# eeZeePower.net
KiCad netlist of a schematic drawn in EAGLE
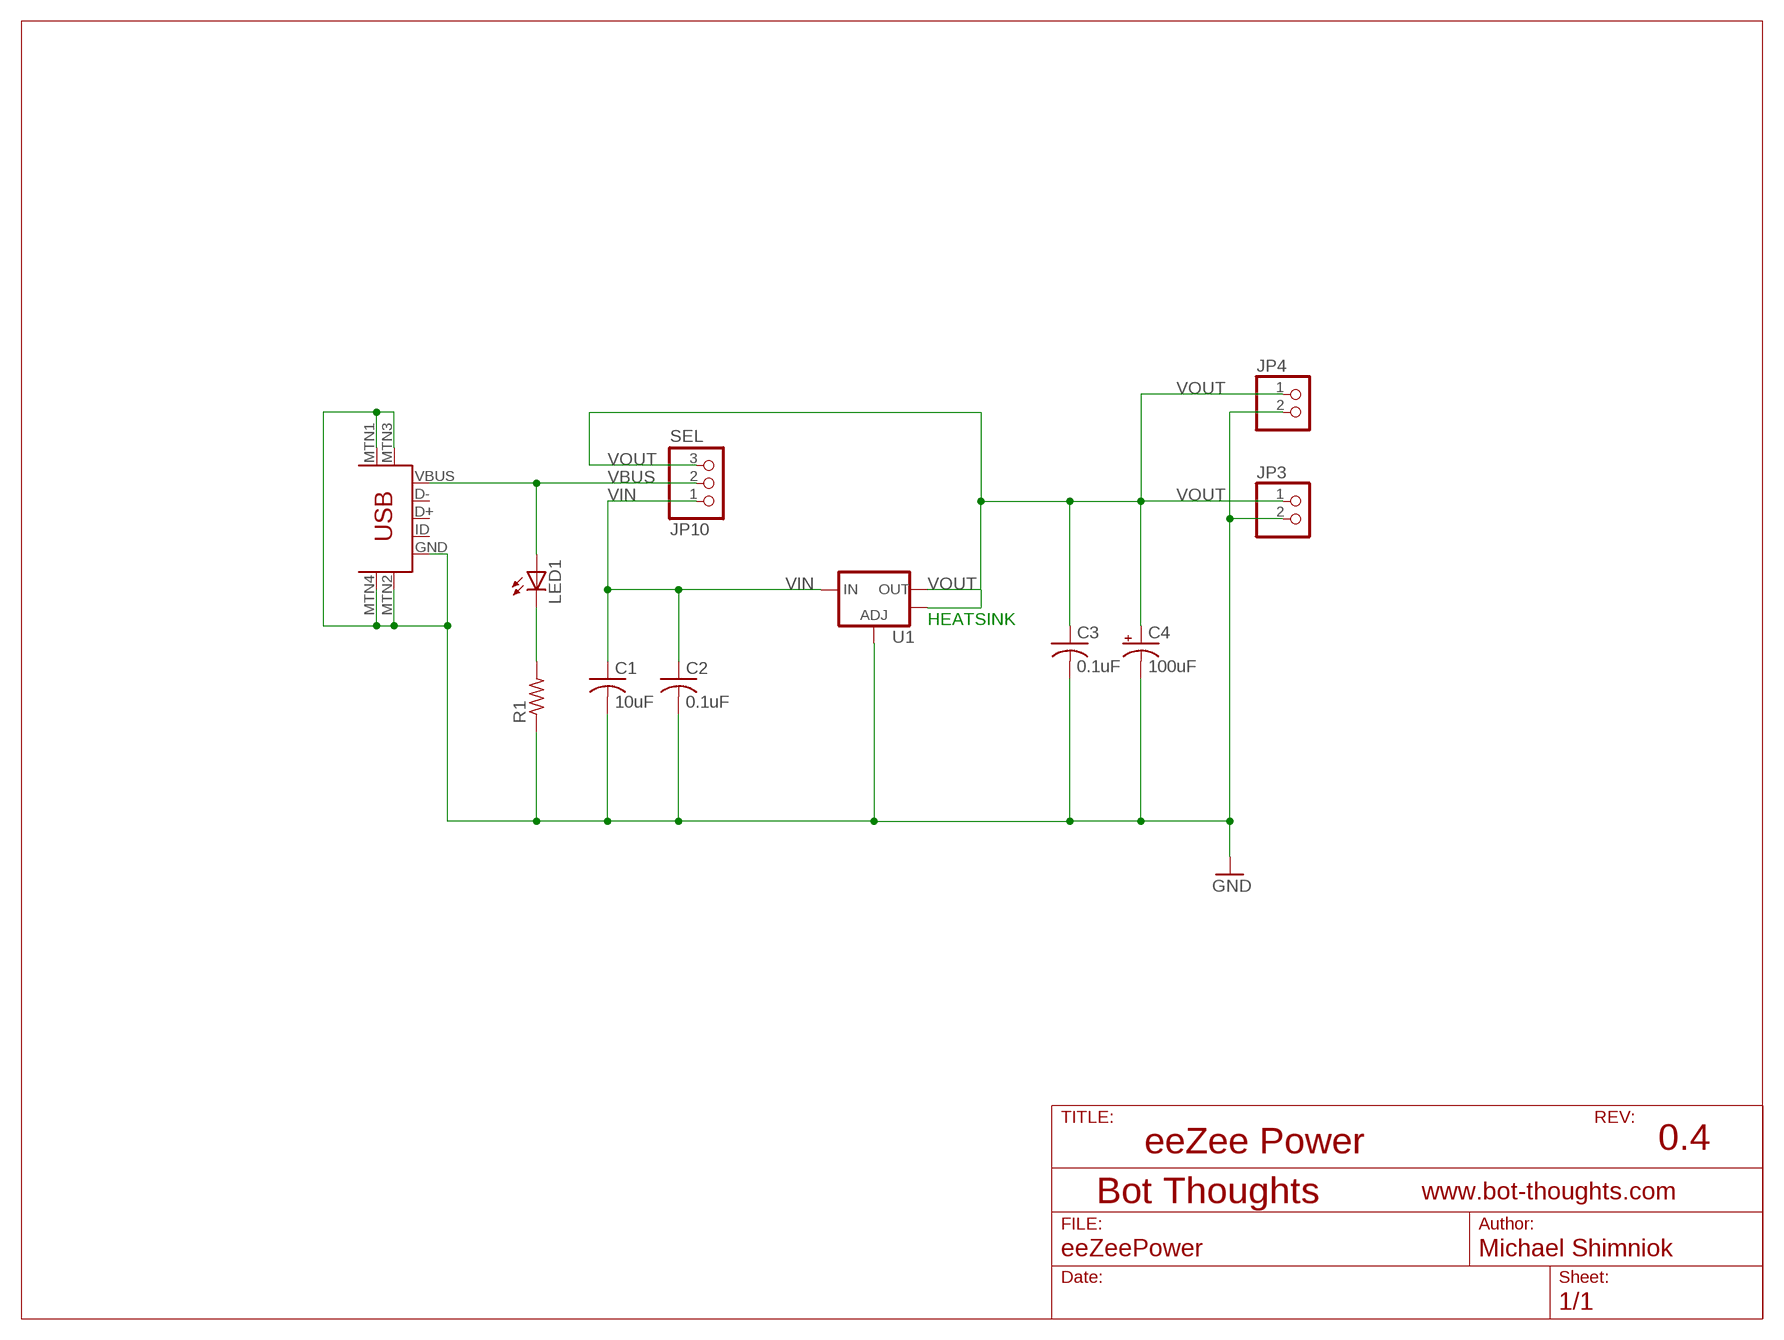
[diagram p0: schematic, sheet 1]

(export (version "E")
  (design (tool "Eeschema 10.0.6"))
  (components
    (comp (ref "C1")
      (value "10uF")
      (footprint "eagle-import:C1206")
      (libsource (lib "eagle-import") (part "C-USC1206"))
    )
    (comp (ref "C2")
      (value "0.1uF")
      (footprint "eagle-import:C0603")
      (libsource (lib "eagle-import") (part "C-USC0603"))
    )
    (comp (ref "C3")
      (value "0.1uF")
      (footprint "eagle-import:C0603")
      (libsource (lib "eagle-import") (part "C-USC0603"))
    )
    (comp (ref "C4")
      (value "100uF")
      (footprint "eagle-import:SMC_B")
      (libsource (lib "eagle-import") (part "CPOL-USSMCB"))
    )
    (comp (ref "JP3")
      (value "PINHD-1X02_2.54-S")
      (footprint "eagle-import:1X02-S")
      (libsource (lib "eagle-import") (part "PINHD-1X02_2.54-S"))
    )
    (comp (ref "JP4")
      (value "PINHD-1X02_2.54-S")
      (footprint "eagle-import:1X02-S")
      (libsource (lib "eagle-import") (part "PINHD-1X02_2.54-S"))
    )
    (comp (ref "JP10")
      (value "SEL")
      (footprint "eagle-import:1X03-S")
      (libsource (lib "eagle-import") (part "PINHD-1X03_2.54-S"))
    )
    (comp (ref "LED1")
      (value "LEDCHIPLED_1206")
      (footprint "eagle-import:CHIPLED_1206")
      (libsource (lib "eagle-import") (part "LEDCHIPLED_1206"))
    )
    (comp (ref "R1")
      (value "R-US_R0603")
      (footprint "eagle-import:R0603")
      (libsource (lib "eagle-import") (part "R-US_R0603"))
    )
    (comp (ref "U$1")
      (value "USB-MINIB-5PIN")
      (footprint "eagle-import:USB-MINIB")
      (libsource (lib "eagle-import") (part "USB-MINIB-5PIN"))
    )
    (comp (ref "U1")
      (value "V_REG_LM1117SOT223")
      (footprint "eagle-import:SOT223")
      (libsource (lib "eagle-import") (part "V_REG_LM1117SOT223"))
    )
  )
  (nets
    (net (code "1") (name "/VBUS") (class "Default")
      (node (ref "JP10") (pin "2") (pinfunction "2_2") (pintype "passive"))
      (node (ref "LED1") (pin "A") (pinfunction "A_A") (pintype "passive"))
      (node (ref "U$1") (pin "VBUS") (pinfunction "VBUS_VBUS") (pintype "bidirectional"))
    )
    (net (code "2") (name "/VIN") (class "Default")
      (node (ref "C1") (pin "1") (pinfunction "1_1") (pintype "passive"))
      (node (ref "C2") (pin "1") (pinfunction "1_1") (pintype "passive"))
      (node (ref "JP10") (pin "1") (pinfunction "1_1") (pintype "passive"))
      (node (ref "U1") (pin "3") (pinfunction "IN_3") (pintype "input"))
    )
    (net (code "3") (name "/VOUT") (class "Default")
      (node (ref "C3") (pin "1") (pinfunction "1_1") (pintype "passive"))
      (node (ref "C4") (pin "+") (pinfunction "+_+") (pintype "passive"))
      (node (ref "JP10") (pin "3") (pinfunction "3_3") (pintype "passive"))
      (node (ref "JP3") (pin "1") (pinfunction "1_1") (pintype "passive"))
      (node (ref "JP4") (pin "1") (pinfunction "1_1") (pintype "passive"))
      (node (ref "U1") (pin "2") (pinfunction "OUT_2") (pintype "output"))
      (node (ref "U1") (pin "4") (pinfunction "OUT_4") (pintype "output"))
    )
    (net (code "4") (name "GND") (class "Default")
      (node (ref "C1") (pin "2") (pinfunction "2_2") (pintype "passive"))
      (node (ref "C2") (pin "2") (pinfunction "2_2") (pintype "passive"))
      (node (ref "C3") (pin "2") (pinfunction "2_2") (pintype "passive"))
      (node (ref "C4") (pin "-") (pinfunction "-_-") (pintype "passive"))
      (node (ref "JP3") (pin "2") (pinfunction "2_2") (pintype "passive"))
      (node (ref "JP4") (pin "2") (pinfunction "2_2") (pintype "passive"))
      (node (ref "R1") (pin "1") (pinfunction "1_1") (pintype "passive"))
      (node (ref "U$1") (pin "GND") (pinfunction "GND_GND") (pintype "bidirectional"))
      (node (ref "U$1") (pin "MTN1") (pinfunction "MTN2_MTN1") (pintype "bidirectional"))
      (node (ref "U$1") (pin "MTN2") (pinfunction "MTN3_MTN2") (pintype "bidirectional"))
      (node (ref "U$1") (pin "MTN3") (pinfunction "MTN1_MTN3") (pintype "bidirectional"))
      (node (ref "U$1") (pin "MTN4") (pinfunction "MTN4_MTN4") (pintype "bidirectional"))
      (node (ref "U1") (pin "1") (pinfunction "ADJ_1") (pintype "input"))
    )
    (net (code "5") (name "Net-(LED1-PadC)") (class "Default")
      (node (ref "LED1") (pin "C") (pinfunction "C_C") (pintype "passive"))
      (node (ref "R1") (pin "2") (pinfunction "2_2") (pintype "passive"))
    )
    (net (code "6") (name "unconnected-(U$1-PadD+)") (class "Default")
      (node (ref "U$1") (pin "D+") (pinfunction "D+_D+") (pintype "bidirectional"))
    )
    (net (code "7") (name "unconnected-(U$1-PadD-)") (class "Default")
      (node (ref "U$1") (pin "D-") (pinfunction "D-_D-") (pintype "bidirectional"))
    )
    (net (code "8") (name "unconnected-(U$1-PadID)") (class "Default")
      (node (ref "U$1") (pin "ID") (pinfunction "ID_ID") (pintype "bidirectional"))
    )
  )
)
